# 3V3_LDO_Regulator.net
KiCad netlist of a schematic drawn in Altium Designer
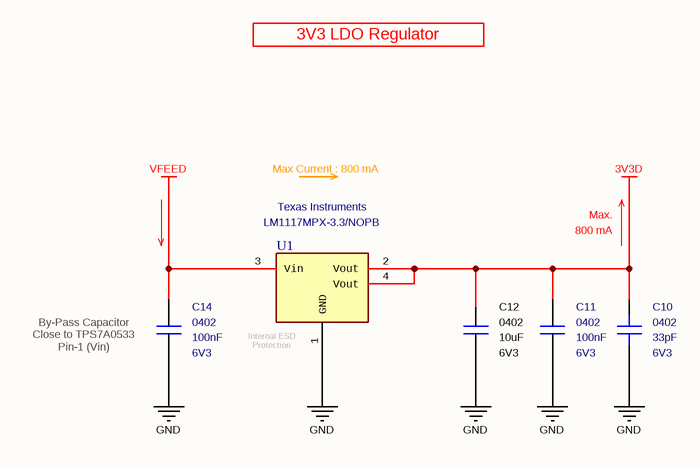
[diagram p0: 3V3 LDO Regulator.SchDoc]

(export (version "E")
  (design (tool "Eeschema 10.0.6"))
  (components
    (comp (ref "C10")
      (value "33pF")
      (footprint "CAPACITOR_0402")
      (description "Capacitor - 33pF [0402] (Ceramic)")
      (fields
        (field (name "MANUFACTURER_PART_NUMBER") "C0402C330J9RACAUTO")
        (field (name "MOUSER_PART_NUMBER") "80-C0402C330J9RAUTO")
        (field (name "CASE") "0402")
        (field (name "VOLTAGE") "6V3")
      )
      (libsource (lib "Ovoo_Schematic") (part "Capacitor - 33pF [0402-6V3]"))
    )
    (comp (ref "C11")
      (value "100nF")
      (footprint "CAPACITOR_0402")
      (description "Capacitor - 100nF [0402-6V3] (Ceramic)")
      (fields
        (field (name "MANUFACTURER_PART_NUMBER") "04026D104KAT4A")
        (field (name "MOUSER_PART_NUMBER") "581-04026D104KAT4A")
        (field (name "CASE") "0402")
        (field (name "VOLTAGE") "6V3")
      )
      (libsource (lib "Ovoo_Schematic") (part "Capacitor - 100nF [0402-6V3]"))
    )
    (comp (ref "C12")
      (value "10uF")
      (footprint "CAPACITOR_0402")
      (description "Capacitor - 10uF [0402] (Ceramic)")
      (fields
        (field (name "MANUFACTURER PART NUMBER") "C0402C106M9PACTU")
        (field (name "MOUSER PART NUMBER") "80-C0402C106M9P")
        (field (name "CASE") "0402")
        (field (name "VOLTAGE") "6V3")
      )
      (libsource (lib "Ovoo_Library") (part "Capacitor - 10uF [0402-6V3]"))
    )
    (comp (ref "C14")
      (value "100nF")
      (footprint "CAPACITOR_0402")
      (description "Capacitor - 100nF [0402-6V3] (Ceramic)")
      (fields
        (field (name "MANUFACTURER_PART_NUMBER") "04026D104KAT4A")
        (field (name "MOUSER_PART_NUMBER") "581-04026D104KAT4A")
        (field (name "CASE") "0402")
        (field (name "VOLTAGE") "6V3")
      )
      (libsource (lib "Ovoo_Schematic") (part "Capacitor - 100nF [0402-6V3]"))
    )
    (comp (ref "U1")
      (value "LDO Voltage Regulator")
      (footprint "SOT-223-4")
      (description "LDO Voltage Regulators 800MA LDO LINEAR REG")
      (fields
        (field (name "MOUSER PART NUMBER") "926-LM1117MPX3.3NOPB")
        (field (name "MANUFACTURER PART NUMBER") "LM1117MPX-3.3/NOPB")
        (field (name "MANUFACTURER NAME") "Texas Instruments")
      )
      (libsource (lib "Ovoo_Library") (part "IC - LM1117MPX-3.3/NOPB"))
    )
  )
  (nets
    (net (code "1") (name "3V3D") (class "Default")
      (node (ref "C10") (pin "1") (pinfunction "1_1") (pintype "passive"))
      (node (ref "C11") (pin "1") (pinfunction "1_1") (pintype "passive"))
      (node (ref "C12") (pin "2") (pinfunction "2_2") (pintype "passive"))
      (node (ref "U1") (pin "2") (pinfunction "Vout_2") (pintype "power_in"))
      (node (ref "U1") (pin "4") (pinfunction "Vout_4") (pintype "power_in"))
    )
    (net (code "2") (name "GND") (class "Default")
      (node (ref "C10") (pin "2") (pinfunction "2_2") (pintype "passive"))
      (node (ref "C11") (pin "2") (pinfunction "2_2") (pintype "passive"))
      (node (ref "C12") (pin "1") (pinfunction "1_1") (pintype "passive"))
      (node (ref "C14") (pin "2") (pinfunction "2_2") (pintype "passive"))
      (node (ref "U1") (pin "1") (pinfunction "GND_1") (pintype "power_in"))
    )
    (net (code "3") (name "VFEED") (class "Default")
      (node (ref "C14") (pin "1") (pinfunction "1_1") (pintype "passive"))
      (node (ref "U1") (pin "3") (pinfunction "Vin_3") (pintype "power_in"))
    )
  )
)
